# 05_ESP32.net
KiCad netlist of a schematic drawn in Altium Designer
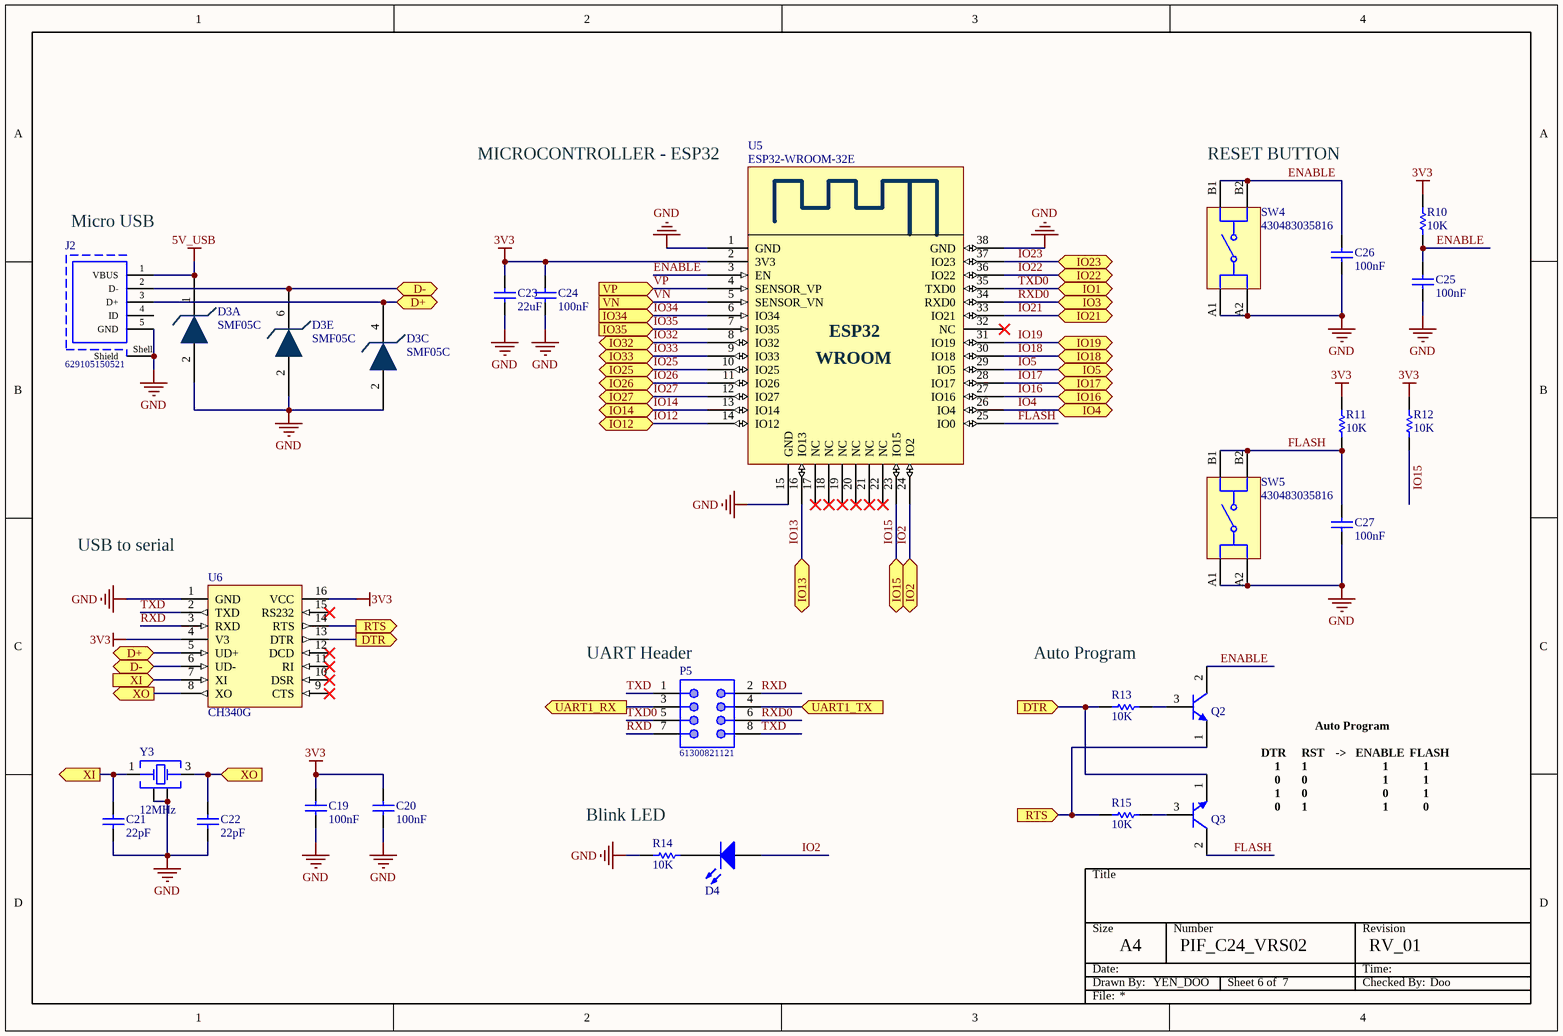
[diagram p0: 05_ESP32.SchDoc]

(export (version "E")
  (design (tool "Eeschema 10.0.6"))
  (components
    (comp (ref "C19")
      (value "100nF")
      (footprint "CAP-SM-0805")
      (description "Capacitor")
      (fields (field (name "Comment") "Cap Non-Pol SMD"))
      (libsource (lib "PIF_Library") (part "Cap Non-Pol SMD"))
    )
    (comp (ref "C20")
      (value "100nF")
      (footprint "CAP-SM-0805")
      (description "Capacitor")
      (fields (field (name "Comment") "Cap Non-Pol SMD"))
      (libsource (lib "PIF_Library") (part "Cap Non-Pol SMD"))
    )
    (comp (ref "C21")
      (value "22pF")
      (footprint "CAP-SM-0805")
      (description "Capacitor")
      (fields (field (name "Comment") "Cap Non-Pol SMD"))
      (libsource (lib "PIF_Library") (part "Cap Non-Pol SMD"))
    )
    (comp (ref "C22")
      (value "22pF")
      (footprint "CAP-SM-0805")
      (description "Capacitor")
      (fields (field (name "Comment") "Cap Non-Pol SMD"))
      (libsource (lib "PIF_Library") (part "Cap Non-Pol SMD"))
    )
    (comp (ref "C23")
      (value "22uF")
      (footprint "CAP-SM-0805")
      (description "Capacitor")
      (fields (field (name "Comment") "Cap Non-Pol SMD"))
      (libsource (lib "PIF_Library") (part "Cap Non-Pol SMD"))
    )
    (comp (ref "C24")
      (value "100nF")
      (footprint "CAP-SM-0805")
      (description "Capacitor")
      (fields (field (name "Comment") "Cap Non-Pol SMD"))
      (libsource (lib "PIF_Library") (part "Cap Non-Pol SMD"))
    )
    (comp (ref "C25")
      (value "100nF")
      (footprint "CAP-SM-0805")
      (description "Capacitor")
      (fields (field (name "Comment") "Cap Non-Pol SMD"))
      (libsource (lib "PIF_Library") (part "Cap Non-Pol SMD"))
    )
    (comp (ref "C26")
      (value "100nF")
      (footprint "CAP-SM-0805")
      (description "Capacitor")
      (fields (field (name "Comment") "Cap Non-Pol SMD"))
      (libsource (lib "PIF_Library") (part "Cap Non-Pol SMD"))
    )
    (comp (ref "C27")
      (value "100nF")
      (footprint "CAP-SM-0805")
      (description "Capacitor")
      (fields (field (name "Comment") "Cap Non-Pol SMD"))
      (libsource (lib "PIF_Library") (part "Cap Non-Pol SMD"))
    )
    (comp (ref "D3")
      (value "SMF05C")
      (footprint "SC70 6L")
      (description "12.5V Clamp 8A (8/20µs) Ipp Tvs Diode Surface Mount SC-70-6")
      (fields (field (name "MFR") "Semtech Corporation"))
      (libsource (lib "YenDoo") (part "SMF05"))
    )
    (comp (ref "D4")
      (value "LED SMD")
      (footprint "LED_0805_Blue")
      (description "LED")
      (libsource (lib "PIF_Library") (part "LED SMD"))
    )
    (comp (ref "J2")
      (value "629105150521")
      (footprint "629105150521")
      (description "Micro USB 2.0 Type B Receptacle WR-COM, Horizontal, SMT, with Pegs, High Current at Pin 1 & Pin 5")
      (fields (field (name "PUBLISHER") "Wurth Elektronik"))
      (libsource (lib "ALTIUM-WR-COM_USB_20-rev18d") (part "629105150521"))
    )
    (comp (ref "P5")
      (value "61300821121")
      (footprint "61300821121")
      (description "WR-PHD Pin Header, THT, pitch 2.54mm, Dual Row, Vertical, 8p")
      (fields (field (name "MANUFACTURER") "Wurth Elektronik"))
      (libsource (lib "Altium_WR-PHD (rev20a)") (part "61300821121"))
    )
    (comp (ref "Q2")
      (value "C1815")
      (footprint "SOT23B")
      (description "NPN Bipolar Transistor")
      (libsource (lib "PIF_Library") (part "C1815"))
    )
    (comp (ref "Q3")
      (value "C1815")
      (footprint "SOT23B")
      (description "NPN Bipolar Transistor")
      (libsource (lib "PIF_Library") (part "C1815"))
    )
    (comp (ref "R10")
      (value "10K")
      (footprint "RES-SM-0805")
      (description "Resistor")
      (fields (field (name "Comment") "RESISTOR SMD"))
      (libsource (lib "PIF_Library") (part "RESISTOR SMD"))
    )
    (comp (ref "R11")
      (value "10K")
      (footprint "RES-SM-0805")
      (description "Resistor")
      (fields (field (name "Comment") "RESISTOR SMD"))
      (libsource (lib "PIF_Library") (part "RESISTOR SMD"))
    )
    (comp (ref "R12")
      (value "10K")
      (footprint "RES-SM-0805")
      (description "Resistor")
      (fields (field (name "Comment") "RESISTOR SMD"))
      (libsource (lib "PIF_Library") (part "RESISTOR SMD"))
    )
    (comp (ref "R13")
      (value "10K")
      (footprint "RES-SM-0805")
      (description "Resistor")
      (fields (field (name "Comment") "RESISTOR SMD"))
      (libsource (lib "PIF_Library") (part "RESISTOR SMD"))
    )
    (comp (ref "R14")
      (value "10K")
      (footprint "RES-SM-0805")
      (description "Resistor")
      (fields (field (name "Comment") "RESISTOR SMD"))
      (libsource (lib "PIF_Library") (part "RESISTOR SMD"))
    )
    (comp (ref "R15")
      (value "10K")
      (footprint "RES-SM-0805")
      (description "Resistor")
      (fields (field (name "Comment") "RESISTOR SMD"))
      (libsource (lib "PIF_Library") (part "RESISTOR SMD"))
    )
    (comp (ref "SW4")
      (value "430483035816")
      (footprint "WS-TASV_L6W6H3.5_4304x30358x6")
      (description "WS-TASV J-Bend SMT Washable Tact Switch, 12VDC, 50mA, 160g, height 3.5mm")
      (fields (field (name "MANUFACTURER") "Wurth Elektronik"))
      (libsource (lib "Altium_WS-TASV (rev22a)") (part "430483035816"))
    )
    (comp (ref "SW5")
      (value "430483035816")
      (footprint "WS-TASV_L6W6H3.5_4304x30358x6")
      (description "WS-TASV J-Bend SMT Washable Tact Switch, 12VDC, 50mA, 160g, height 3.5mm")
      (fields (field (name "MANUFACTURER") "Wurth Elektronik"))
      (libsource (lib "Altium_WS-TASV (rev22a)") (part "430483035816"))
    )
    (comp (ref "U5")
      (value "ESP32-WROOM-32E")
      (footprint "ESP32-WROOM")
      (fields (field (name "MFR") "Espressif Systems") (field (name "UTILIZED IC / PART") "ESP32-D0WD-V3"))
      (libsource (lib "YenDoo") (part "ESP32-WROOM"))
    )
    (comp (ref "U6")
      (value "CH340G")
      (footprint "DSIP-16")
      (description "USB Bridge, USB to UART USB 2.0 UART Interface")
      (fields (field (name "MFR") "SparkFun Electronics"))
      (libsource (lib "YenDoo") (part "CH340"))
    )
    (comp (ref "Y3")
      (value "12MHz")
      (footprint "WE-XTAL_CFPX-104")
      (description "WE-XTAL Quartz Crystal, SMT, CFPX-104, 12MHz, +/-30ppm")
      (fields
        (field (name "MANUFACTURER PART NUMBER") "830055999")
        (field (name "MANUFACTURER") "Wurth Elektronik")
      )
      (libsource (lib "Altium_WE-XTAL (rev20c)") (part "830055999"))
    )
  )
  (nets
    (net (code "1") (name "/D+") (class "Default")
      (node (ref "D3") (pin "4") (pinfunction "4_4") (pintype "passive"))
      (node (ref "J2") (pin "3") (pinfunction "D+_3") (pintype "passive"))
      (node (ref "U6") (pin "5") (pinfunction "UD+_5") (pintype "input"))
    )
    (net (code "2") (name "/D-") (class "Default")
      (node (ref "D3") (pin "6") (pinfunction "6_6") (pintype "passive"))
      (node (ref "J2") (pin "2") (pinfunction "D-_2") (pintype "passive"))
      (node (ref "U6") (pin "6") (pinfunction "UD-_6") (pintype "input"))
    )
    (net (code "3") (name "/DTR") (class "Default")
      (node (ref "Q3") (pin "1") (pinfunction "E_1") (pintype "passive"))
      (node (ref "R13") (pin "2") (pinfunction "2_2") (pintype "passive"))
      (node (ref "U6") (pin "13") (pinfunction "DTR_13") (pintype "output"))
    )
    (net (code "4") (name "/ENABLE") (class "Default")
      (node (ref "C25") (pin "2") (pinfunction "2_2") (pintype "passive"))
      (node (ref "C26") (pin "2") (pinfunction "2_2") (pintype "passive"))
      (node (ref "Q2") (pin "2") (pinfunction "C_2") (pintype "passive"))
      (node (ref "R10") (pin "1") (pinfunction "1_1") (pintype "passive"))
      (node (ref "SW4") (pin "B1") (pinfunction "B1_B1") (pintype "passive"))
      (node (ref "SW4") (pin "B2") (pinfunction "B2_B2") (pintype "passive"))
      (node (ref "U5") (pin "3") (pinfunction "EN_3") (pintype "input"))
    )
    (net (code "5") (name "/FLASH") (class "Default")
      (node (ref "C27") (pin "2") (pinfunction "2_2") (pintype "passive"))
      (node (ref "Q3") (pin "2") (pinfunction "C_2") (pintype "passive"))
      (node (ref "R11") (pin "1") (pinfunction "1_1") (pintype "passive"))
      (node (ref "SW5") (pin "B1") (pinfunction "B1_B1") (pintype "passive"))
      (node (ref "SW5") (pin "B2") (pinfunction "B2_B2") (pintype "passive"))
      (node (ref "U5") (pin "25") (pinfunction "IO0_25") (pintype "bidirectional"))
    )
    (net (code "6") (name "/IO2") (class "Default")
      (node (ref "D4") (pin "1") (pinfunction "A_1") (pintype "passive"))
      (node (ref "U5") (pin "24") (pinfunction "IO2_24") (pintype "bidirectional"))
    )
    (net (code "7") (name "/IO4") (class "Default")
      (node (ref "U5") (pin "26") (pinfunction "IO4_26") (pintype "bidirectional"))
    )
    (net (code "8") (name "/IO5") (class "Default")
      (node (ref "U5") (pin "29") (pinfunction "IO5_29") (pintype "bidirectional"))
    )
    (net (code "9") (name "/IO12") (class "Default")
      (node (ref "U5") (pin "14") (pinfunction "IO12_14") (pintype "bidirectional"))
    )
    (net (code "10") (name "/IO13") (class "Default")
      (node (ref "U5") (pin "16") (pinfunction "IO13_16") (pintype "bidirectional"))
    )
    (net (code "11") (name "/IO14") (class "Default")
      (node (ref "U5") (pin "13") (pinfunction "IO14_13") (pintype "bidirectional"))
    )
    (net (code "12") (name "/IO15") (class "Default")
      (node (ref "R12") (pin "1") (pinfunction "1_1") (pintype "passive"))
      (node (ref "U5") (pin "23") (pinfunction "IO15_23") (pintype "bidirectional"))
    )
    (net (code "13") (name "/IO16") (class "Default")
      (node (ref "U5") (pin "27") (pinfunction "IO16_27") (pintype "bidirectional"))
    )
    (net (code "14") (name "/IO17") (class "Default")
      (node (ref "U5") (pin "28") (pinfunction "IO17_28") (pintype "bidirectional"))
    )
    (net (code "15") (name "/IO18") (class "Default")
      (node (ref "U5") (pin "30") (pinfunction "IO18_30") (pintype "bidirectional"))
    )
    (net (code "16") (name "/IO19") (class "Default")
      (node (ref "U5") (pin "31") (pinfunction "IO19_31") (pintype "bidirectional"))
    )
    (net (code "17") (name "/IO21") (class "Default")
      (node (ref "U5") (pin "33") (pinfunction "IO21_33") (pintype "bidirectional"))
    )
    (net (code "18") (name "/IO22") (class "Default")
      (node (ref "U5") (pin "36") (pinfunction "IO22_36") (pintype "bidirectional"))
    )
    (net (code "19") (name "/IO23") (class "Default")
      (node (ref "U5") (pin "37") (pinfunction "IO23_37") (pintype "bidirectional"))
    )
    (net (code "20") (name "/IO25") (class "Default")
      (node (ref "U5") (pin "10") (pinfunction "IO25_10") (pintype "bidirectional"))
    )
    (net (code "21") (name "/IO26") (class "Default")
      (node (ref "U5") (pin "11") (pinfunction "IO26_11") (pintype "bidirectional"))
    )
    (net (code "22") (name "/IO27") (class "Default")
      (node (ref "U5") (pin "12") (pinfunction "IO27_12") (pintype "bidirectional"))
    )
    (net (code "23") (name "/IO32") (class "Default")
      (node (ref "U5") (pin "8") (pinfunction "IO32_8") (pintype "bidirectional"))
    )
    (net (code "24") (name "/IO33") (class "Default")
      (node (ref "U5") (pin "9") (pinfunction "IO33_9") (pintype "bidirectional"))
    )
    (net (code "25") (name "/IO34") (class "Default")
      (node (ref "U5") (pin "6") (pinfunction "IO34_6") (pintype "input"))
    )
    (net (code "26") (name "/IO35") (class "Default")
      (node (ref "U5") (pin "7") (pinfunction "IO35_7") (pintype "input"))
    )
    (net (code "27") (name "/RTS") (class "Default")
      (node (ref "Q2") (pin "1") (pinfunction "E_1") (pintype "passive"))
      (node (ref "R15") (pin "2") (pinfunction "2_2") (pintype "passive"))
      (node (ref "U6") (pin "14") (pinfunction "RTS_14") (pintype "output"))
    )
    (net (code "28") (name "/RXD") (class "Default")
      (node (ref "P5") (pin "2") (pinfunction "2_2") (pintype "passive"))
      (node (ref "P5") (pin "7") (pinfunction "7_7") (pintype "passive"))
      (node (ref "U6") (pin "3") (pinfunction "RXD_3") (pintype "input"))
    )
    (net (code "29") (name "/RXD0") (class "Default")
      (node (ref "P5") (pin "6") (pinfunction "6_6") (pintype "passive"))
      (node (ref "U5") (pin "34") (pinfunction "RXD0_34") (pintype "bidirectional"))
    )
    (net (code "30") (name "/TXD") (class "Default")
      (node (ref "P5") (pin "1") (pinfunction "1_1") (pintype "passive"))
      (node (ref "P5") (pin "8") (pinfunction "8_8") (pintype "passive"))
      (node (ref "U6") (pin "2") (pinfunction "TXD_2") (pintype "output"))
    )
    (net (code "31") (name "/TXD0") (class "Default")
      (node (ref "P5") (pin "5") (pinfunction "5_5") (pintype "passive"))
      (node (ref "U5") (pin "35") (pinfunction "TXD0_35") (pintype "bidirectional"))
    )
    (net (code "32") (name "/UART1_RX") (class "Default")
      (node (ref "P5") (pin "3") (pinfunction "3_3") (pintype "passive"))
    )
    (net (code "33") (name "/UART1_TX") (class "Default")
      (node (ref "P5") (pin "4") (pinfunction "4_4") (pintype "passive"))
    )
    (net (code "34") (name "/VN") (class "Default")
      (node (ref "U5") (pin "5") (pinfunction "SENSOR_VN_5") (pintype "input"))
    )
    (net (code "35") (name "/VP") (class "Default")
      (node (ref "U5") (pin "4") (pinfunction "SENSOR_VP_4") (pintype "input"))
    )
    (net (code "36") (name "/XI") (class "Default")
      (node (ref "C21") (pin "2") (pinfunction "2_2") (pintype "passive"))
      (node (ref "U6") (pin "7") (pinfunction "XI_7") (pintype "input"))
      (node (ref "Y3") (pin "1") (pinfunction "Crystal_1") (pintype "passive"))
    )
    (net (code "37") (name "/XO") (class "Default")
      (node (ref "C22") (pin "2") (pinfunction "2_2") (pintype "passive"))
      (node (ref "U6") (pin "8") (pinfunction "XO_8") (pintype "output"))
      (node (ref "Y3") (pin "3") (pinfunction "Crystal_3") (pintype "passive"))
    )
    (net (code "38") (name "3V3") (class "Default")
      (node (ref "C19") (pin "2") (pinfunction "2_2") (pintype "passive"))
      (node (ref "C20") (pin "2") (pinfunction "2_2") (pintype "passive"))
      (node (ref "C23") (pin "2") (pinfunction "2_2") (pintype "passive"))
      (node (ref "C24") (pin "2") (pinfunction "2_2") (pintype "passive"))
      (node (ref "R10") (pin "2") (pinfunction "2_2") (pintype "passive"))
      (node (ref "R11") (pin "2") (pinfunction "2_2") (pintype "passive"))
      (node (ref "R12") (pin "2") (pinfunction "2_2") (pintype "passive"))
      (node (ref "U5") (pin "2") (pinfunction "3V3_2") (pintype "power_in"))
      (node (ref "U6") (pin "16") (pinfunction "VCC_16") (pintype "power_in"))
      (node (ref "U6") (pin "4") (pinfunction "V3_4") (pintype "power_in"))
    )
    (net (code "39") (name "5V_USB") (class "Default")
      (node (ref "D3") (pin "1") (pinfunction "1_1") (pintype "passive"))
      (node (ref "J2") (pin "1") (pinfunction "VBUS_1") (pintype "passive"))
    )
    (net (code "40") (name "GND") (class "Default")
      (node (ref "C19") (pin "1") (pinfunction "1_1") (pintype "passive"))
      (node (ref "C20") (pin "1") (pinfunction "1_1") (pintype "passive"))
      (node (ref "C21") (pin "1") (pinfunction "1_1") (pintype "passive"))
      (node (ref "C22") (pin "1") (pinfunction "1_1") (pintype "passive"))
      (node (ref "C23") (pin "1") (pinfunction "1_1") (pintype "passive"))
      (node (ref "C24") (pin "1") (pinfunction "1_1") (pintype "passive"))
      (node (ref "C25") (pin "1") (pinfunction "1_1") (pintype "passive"))
      (node (ref "C26") (pin "1") (pinfunction "1_1") (pintype "passive"))
      (node (ref "C27") (pin "1") (pinfunction "1_1") (pintype "passive"))
      (node (ref "D3") (pin "2") (pinfunction "COM_2") (pintype "passive"))
      (node (ref "J2") (pin "5") (pinfunction "GND_5") (pintype "passive"))
      (node (ref "J2") (pin "Shell") (pinfunction "Shield_Shell") (pintype "passive"))
      (node (ref "R14") (pin "1") (pinfunction "1_1") (pintype "passive"))
      (node (ref "SW4") (pin "A1") (pinfunction "A1_A1") (pintype "passive"))
      (node (ref "SW4") (pin "A2") (pinfunction "A2_A2") (pintype "passive"))
      (node (ref "SW5") (pin "A1") (pinfunction "A1_A1") (pintype "passive"))
      (node (ref "SW5") (pin "A2") (pinfunction "A2_A2") (pintype "passive"))
      (node (ref "U5") (pin "1") (pinfunction "GND_1") (pintype "power_in"))
      (node (ref "U5") (pin "15") (pinfunction "GND_15") (pintype "power_in"))
      (node (ref "U5") (pin "38") (pinfunction "GND_38") (pintype "bidirectional"))
      (node (ref "U6") (pin "1") (pinfunction "GND_1") (pintype "power_in"))
      (node (ref "Y3") (pin "2") (pinfunction "GND_&_Lid_2") (pintype "passive"))
      (node (ref "Y3") (pin "4") (pinfunction "GND_&_Lid_4") (pintype "passive"))
    )
    (net (code "41") (name "Net-(D4-K)") (class "Default")
      (node (ref "D4") (pin "2") (pinfunction "K_2") (pintype "passive"))
      (node (ref "R14") (pin "2") (pinfunction "2_2") (pintype "passive"))
    )
    (net (code "42") (name "Net-(Q2-B)") (class "Default")
      (node (ref "Q2") (pin "3") (pinfunction "B_3") (pintype "passive"))
      (node (ref "R13") (pin "1") (pinfunction "1_1") (pintype "passive"))
    )
    (net (code "43") (name "Net-(Q3-B)") (class "Default")
      (node (ref "Q3") (pin "3") (pinfunction "B_3") (pintype "passive"))
      (node (ref "R15") (pin "1") (pinfunction "1_1") (pintype "passive"))
    )
    (net (code "44") (name "unconnected-(J2-ID-Pad4)") (class "Default")
      (node (ref "J2") (pin "4") (pinfunction "ID_4") (pintype "passive"))
    )
    (net (code "45") (name "unconnected-(U5-NC-Pad17)") (class "Default")
      (node (ref "U5") (pin "17") (pinfunction "NC_17") (pintype "tri_state+no_connect"))
    )
    (net (code "46") (name "unconnected-(U5-NC-Pad18)") (class "Default")
      (node (ref "U5") (pin "18") (pinfunction "NC_18") (pintype "tri_state+no_connect"))
    )
    (net (code "47") (name "unconnected-(U5-NC-Pad19)") (class "Default")
      (node (ref "U5") (pin "19") (pinfunction "NC_19") (pintype "tri_state+no_connect"))
    )
    (net (code "48") (name "unconnected-(U5-NC-Pad20)") (class "Default")
      (node (ref "U5") (pin "20") (pinfunction "NC_20") (pintype "tri_state+no_connect"))
    )
    (net (code "49") (name "unconnected-(U5-NC-Pad21)") (class "Default")
      (node (ref "U5") (pin "21") (pinfunction "NC_21") (pintype "tri_state+no_connect"))
    )
    (net (code "50") (name "unconnected-(U5-NC-Pad22)") (class "Default")
      (node (ref "U5") (pin "22") (pinfunction "NC_22") (pintype "tri_state+no_connect"))
    )
    (net (code "51") (name "unconnected-(U5-NC-Pad32)") (class "Default")
      (node (ref "U5") (pin "32") (pinfunction "NC_32") (pintype "tri_state+no_connect"))
    )
    (net (code "52") (name "unconnected-(U6-CTS-Pad9)") (class "Default")
      (node (ref "U6") (pin "9") (pinfunction "CTS_9") (pintype "input+no_connect"))
    )
    (net (code "53") (name "unconnected-(U6-DCD-Pad12)") (class "Default")
      (node (ref "U6") (pin "12") (pinfunction "DCD_12") (pintype "input+no_connect"))
    )
    (net (code "54") (name "unconnected-(U6-DSR-Pad10)") (class "Default")
      (node (ref "U6") (pin "10") (pinfunction "DSR_10") (pintype "input+no_connect"))
    )
    (net (code "55") (name "unconnected-(U6-RI-Pad11)") (class "Default")
      (node (ref "U6") (pin "11") (pinfunction "RI_11") (pintype "input+no_connect"))
    )
    (net (code "56") (name "unconnected-(U6-RS232-Pad15)") (class "Default")
      (node (ref "U6") (pin "15") (pinfunction "RS232_15") (pintype "input+no_connect"))
    )
  )
)
